# plug-v21-Make-board-myself-to-test-circu.net
KiCad netlist of a schematic drawn in EAGLE
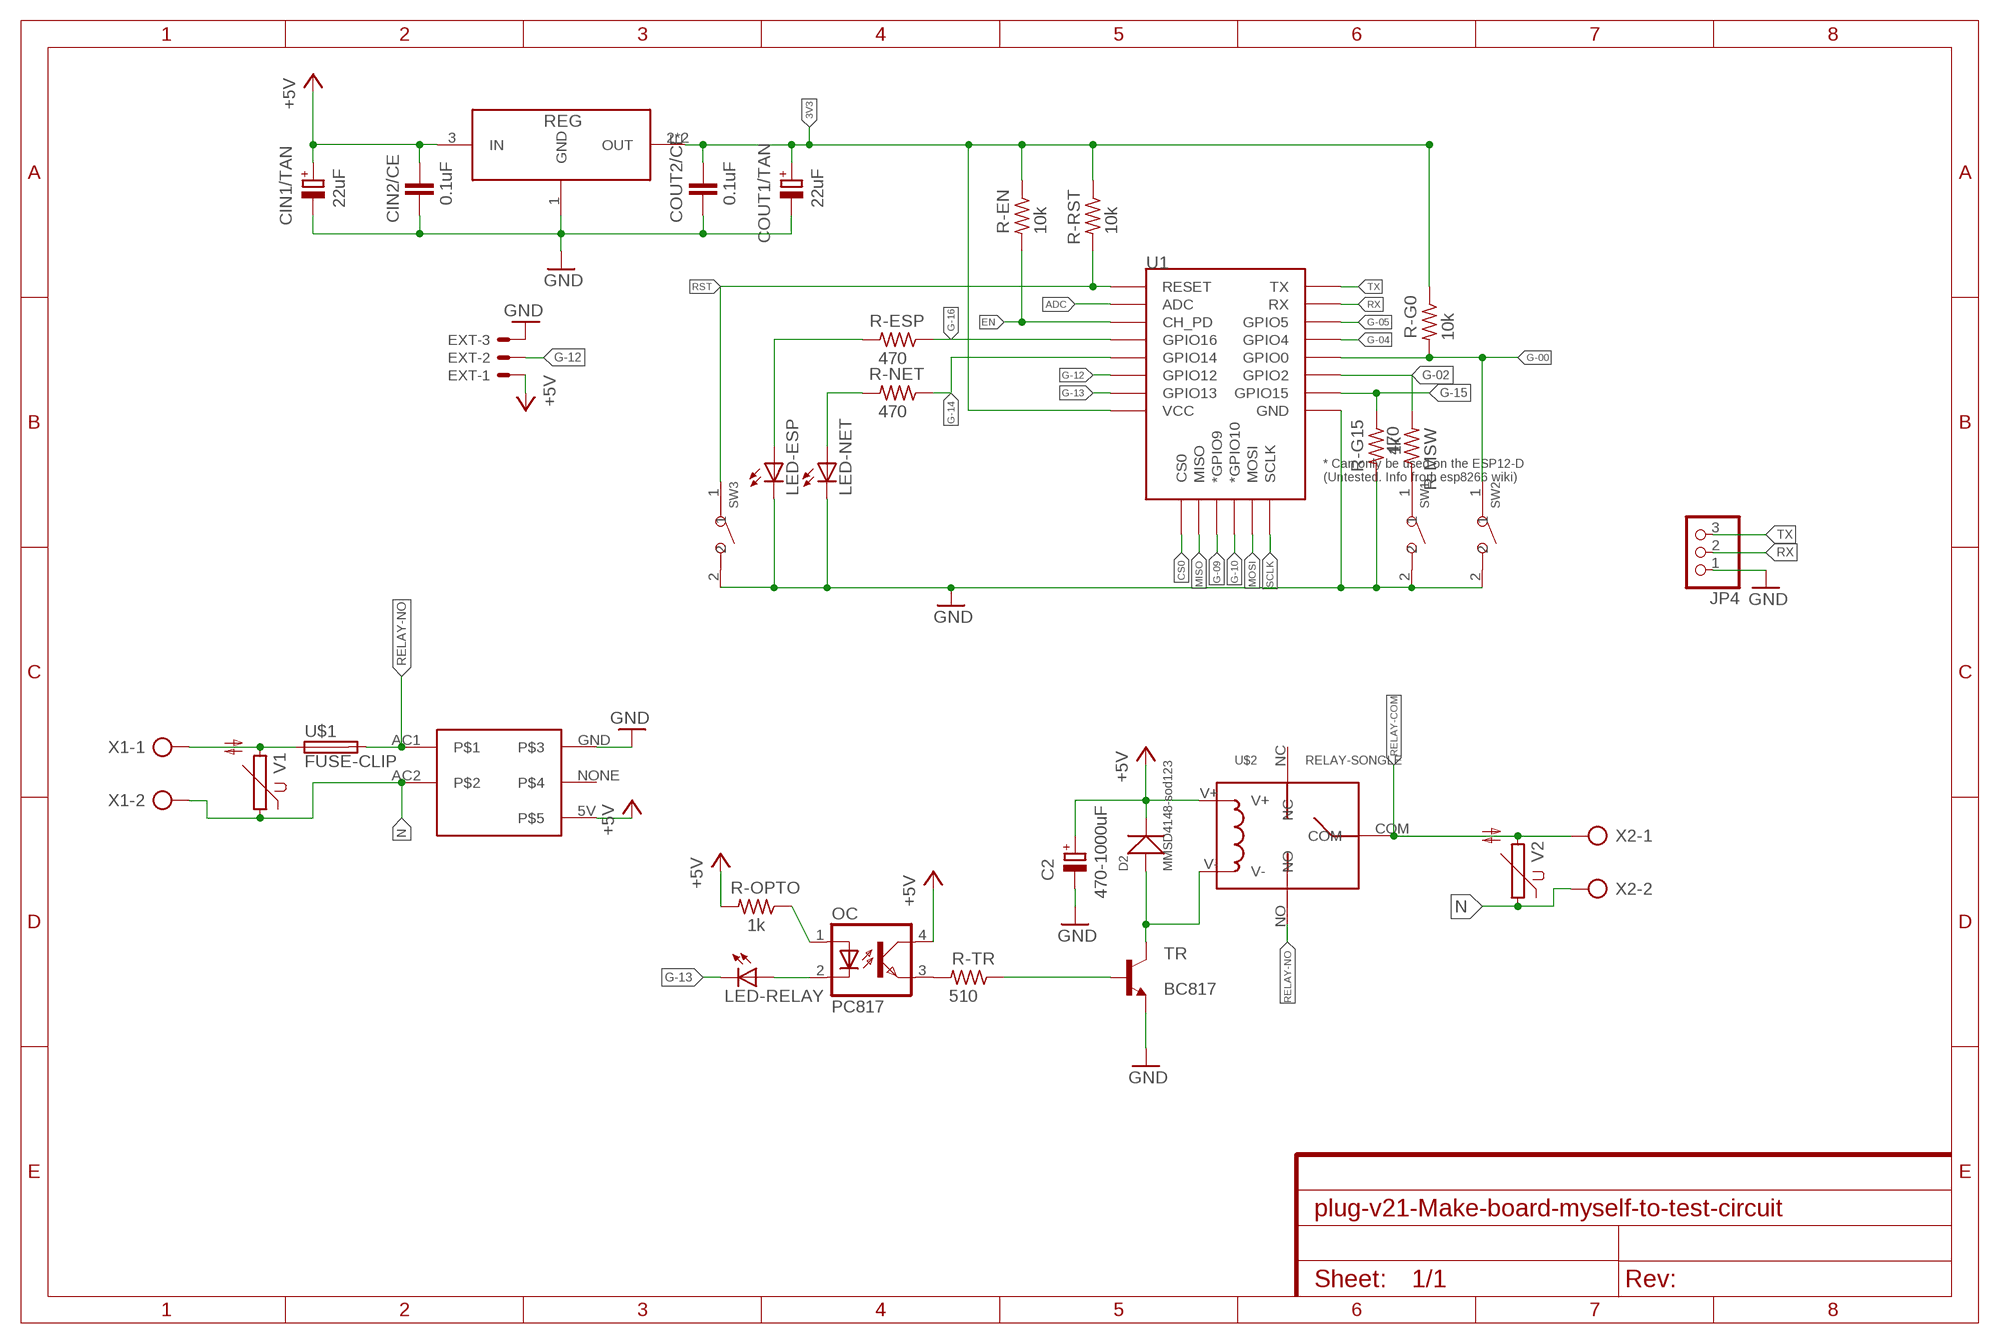
[diagram p0: schematic, sheet 1]

(export (version "E")
  (design (tool "Eeschema 10.0.6"))
  (components
    (comp (ref "C2")
      (value "470-1000uF")
      (footprint "eagle-import:E3,5-8")
      (libsource (lib "eagle-import") (part "CPOL-EUE3.5-8"))
    )
    (comp (ref "CIN1/TAN")
      (value "22uF")
      (footprint "eagle-import:B_3528-21R")
      (libsource (lib "eagle-import") (part "CPOL-EUB/3528-21R"))
    )
    (comp (ref "CIN2/CE")
      (value "0.1uF")
      (footprint "eagle-import:C0805K")
      (libsource (lib "eagle-import") (part "C-EUC0805K"))
    )
    (comp (ref "COUT1/TAN")
      (value "22uF")
      (footprint "eagle-import:B_3528-21R")
      (libsource (lib "eagle-import") (part "CPOL-EUB/3528-21R"))
    )
    (comp (ref "COUT2/CE")
      (value "0.1uF")
      (footprint "eagle-import:C0805K")
      (libsource (lib "eagle-import") (part "C-EUC0805K"))
    )
    (comp (ref "D2")
      (value "MMSD4148-sod123")
      (footprint "eagle-import:SOD-123")
      (fields (field (name "MPN") "MMSD4148"))
      (libsource (lib "eagle-import") (part "SMD-DIODE-100V-200MA(SOD-123)"))
    )
    (comp (ref "EXT")
      (value "53048-03")
      (footprint "eagle-import:53048-03")
      (fields (field (name "MF") "WALDOM/MOLEX") (field (name "MPN") "53048-0310"))
      (libsource (lib "eagle-import") (part "53?-03048"))
    )
    (comp (ref "JP4")
      (value "PINHD-1X3")
      (footprint "eagle-import:1X03")
      (libsource (lib "eagle-import") (part "PINHD-1X3"))
    )
    (comp (ref "LED-ESP")
      (value "LEDCHIPLED_0805")
      (footprint "eagle-import:CHIPLED_0805")
      (libsource (lib "eagle-import") (part "LEDCHIPLED_0805"))
    )
    (comp (ref "LED-NET")
      (value "LEDCHIPLED_0805")
      (footprint "eagle-import:CHIPLED_0805")
      (libsource (lib "eagle-import") (part "LEDCHIPLED_0805"))
    )
    (comp (ref "LED-RELAY")
      (value "LEDCHIPLED_0805")
      (footprint "eagle-import:CHIPLED_0805")
      (libsource (lib "eagle-import") (part "LEDCHIPLED_0805"))
    )
    (comp (ref "OC")
      (value "PC817")
      (footprint "eagle-import:DIL04")
      (fields (field (name "MPN") "PC817X4J000F"))
      (libsource (lib "eagle-import") (part "PC817"))
    )
    (comp (ref "R-EN")
      (value "10k")
      (footprint "eagle-import:M0805")
      (libsource (lib "eagle-import") (part "R-US_M0805"))
    )
    (comp (ref "R-ESP")
      (value "470")
      (footprint "eagle-import:M0805")
      (libsource (lib "eagle-import") (part "R-US_M0805"))
    )
    (comp (ref "R-G0")
      (value "10k")
      (footprint "eagle-import:M0805")
      (libsource (lib "eagle-import") (part "R-US_M0805"))
    )
    (comp (ref "R-G15")
      (value "1k")
      (footprint "eagle-import:M0805")
      (libsource (lib "eagle-import") (part "R-US_M0805"))
    )
    (comp (ref "R-MSW")
      (value "470")
      (footprint "eagle-import:M0805")
      (libsource (lib "eagle-import") (part "R-US_M0805"))
    )
    (comp (ref "R-NET")
      (value "470")
      (footprint "eagle-import:M0805")
      (libsource (lib "eagle-import") (part "R-US_M0805"))
    )
    (comp (ref "R-OPTO")
      (value "1k")
      (footprint "eagle-import:M0805")
      (libsource (lib "eagle-import") (part "R-US_M0805"))
    )
    (comp (ref "R-RST")
      (value "10k")
      (footprint "eagle-import:M0805")
      (libsource (lib "eagle-import") (part "R-US_M0805"))
    )
    (comp (ref "R-TR")
      (value "510")
      (footprint "eagle-import:M0805")
      (libsource (lib "eagle-import") (part "R-US_M0805"))
    )
    (comp (ref "REG")
      (value "AMS1117-3.3")
      (footprint "eagle-import:SOT-223")
      (libsource (lib "eagle-import") (part "AMS1117-3.3"))
    )
    (comp (ref "SW1")
      (value "DIP-BUTTON(2P-6.0X3.0X4.3MM)-TS-1101F")
      (footprint "eagle-import:SW2-5.0-6.0X3.0X4.3MM")
      (libsource (lib "eagle-import") (part "DIP-BUTTON(2P-6.0X3.0X4.3MM)-TS-1101F"))
    )
    (comp (ref "SW2")
      (value "DIP-BUTTON(2P-6.0X3.0X4.3MM)-TS-1101F")
      (footprint "eagle-import:SW2-5.0-6.0X3.0X4.3MM")
      (libsource (lib "eagle-import") (part "DIP-BUTTON(2P-6.0X3.0X4.3MM)-TS-1101F"))
    )
    (comp (ref "SW3")
      (value "DIP-BUTTON(2P-6.0X3.0X4.3MM)-TS-1101F")
      (footprint "eagle-import:SW2-5.0-6.0X3.0X4.3MM")
      (libsource (lib "eagle-import") (part "DIP-BUTTON(2P-6.0X3.0X4.3MM)-TS-1101F"))
    )
    (comp (ref "TR")
      (value "BC817")
      (footprint "eagle-import:SOT23-BEC")
      (libsource (lib "eagle-import") (part "BC817SMD-16"))
    )
    (comp (ref "U$1")
      (value "FUSE-CLIP")
      (footprint "eagle-import:FUSE-CLIP")
      (libsource (lib "eagle-import") (part "FUSE-CLIP"))
    )
    (comp (ref "U$2")
      (value "RELAY-SONGLE")
      (footprint "eagle-import:RELAY-SONGLE")
      (libsource (lib "eagle-import") (part "RELAY-SONGLE"))
    )
    (comp (ref "U$4")
      (value "POWERSUPPLY-5V-700MA")
      (footprint "eagle-import:POWERSUPPLY-5V-700MA")
      (libsource (lib "eagle-import") (part "POWERSUPPLY-5V-700MA"))
    )
    (comp (ref "U1")
      (value "ESP12ESMD")
      (footprint "eagle-import:ESP12E-SMD")
      (libsource (lib "eagle-import") (part "ESP12ESMD"))
    )
    (comp (ref "V1")
      (value "S14K11")
      (footprint "eagle-import:S14K11")
      (libsource (lib "eagle-import") (part "S14K11"))
    )
    (comp (ref "V2")
      (value "S14K11")
      (footprint "eagle-import:S14K11")
      (libsource (lib "eagle-import") (part "S14K11"))
    )
    (comp (ref "X1")
      (value "AK300/2")
      (footprint "eagle-import:AK300_2")
      (libsource (lib "eagle-import") (part "AK300/2"))
    )
    (comp (ref "X2")
      (value "AK300/2")
      (footprint "eagle-import:AK300_2")
      (libsource (lib "eagle-import") (part "AK300/2"))
    )
  )
  (nets
    (net (code "1") (name "+5V") (class "Default")
      (node (ref "C2") (pin "+") (pinfunction "+_+") (pintype "passive"))
      (node (ref "CIN1/TAN") (pin "+") (pinfunction "+_+") (pintype "passive"))
      (node (ref "CIN2/CE") (pin "1") (pinfunction "1_1") (pintype "passive"))
      (node (ref "D2") (pin "-") (pinfunction "-_-") (pintype "passive"))
      (node (ref "EXT") (pin "1") (pinfunction "S_1") (pintype "passive"))
      (node (ref "OC") (pin "4") (pinfunction "COL_4") (pintype "passive"))
      (node (ref "R-OPTO") (pin "2") (pinfunction "2_2") (pintype "passive"))
      (node (ref "REG") (pin "3") (pinfunction "IN_3") (pintype "input"))
      (node (ref "U$2") (pin "V+") (pinfunction "V+_V+") (pintype "bidirectional"))
      (node (ref "U$4") (pin "5V") (pinfunction "P$5_5V") (pintype "bidirectional"))
    )
    (net (code "2") (name "3V3") (class "Default")
      (node (ref "COUT1/TAN") (pin "+") (pinfunction "+_+") (pintype "passive"))
      (node (ref "COUT2/CE") (pin "1") (pinfunction "1_1") (pintype "passive"))
      (node (ref "R-EN") (pin "1") (pinfunction "1_1") (pintype "passive"))
      (node (ref "R-G0") (pin "1") (pinfunction "1_1") (pintype "passive"))
      (node (ref "R-RST") (pin "1") (pinfunction "1_1") (pintype "passive"))
      (node (ref "REG") (pin "2") (pinfunction "OUT_2") (pintype "output"))
      (node (ref "REG") (pin "4") (pinfunction "OUT_4") (pintype "output"))
      (node (ref "U1") (pin "VCC") (pinfunction "VCC_VCC") (pintype "bidirectional"))
    )
    (net (code "3") (name "ADC") (class "Default")
      (node (ref "U1") (pin "ADC") (pinfunction "ADC_ADC") (pintype "bidirectional"))
    )
    (net (code "4") (name "CS0") (class "Default")
      (node (ref "U1") (pin "CS0") (pinfunction "CS0_CS0") (pintype "bidirectional"))
    )
    (net (code "5") (name "EN") (class "Default")
      (node (ref "R-EN") (pin "2") (pinfunction "2_2") (pintype "passive"))
      (node (ref "U1") (pin "CH_PD") (pinfunction "CH_PD_CH_PD") (pintype "bidirectional"))
    )
    (net (code "6") (name "G-00") (class "Default")
      (node (ref "R-G0") (pin "2") (pinfunction "2_2") (pintype "passive"))
      (node (ref "SW2") (pin "1") (pinfunction "1_1") (pintype "bidirectional"))
      (node (ref "U1") (pin "GPIO0") (pinfunction "GPIO0_GPIO0") (pintype "bidirectional"))
    )
    (net (code "7") (name "G-02") (class "Default")
      (node (ref "R-MSW") (pin "2") (pinfunction "2_2") (pintype "passive"))
      (node (ref "U1") (pin "GPIO2") (pinfunction "GPIO2_GPIO2") (pintype "bidirectional"))
    )
    (net (code "8") (name "G-04") (class "Default")
      (node (ref "U1") (pin "GPIO4") (pinfunction "GPIO4_GPIO4") (pintype "bidirectional"))
    )
    (net (code "9") (name "G-05") (class "Default")
      (node (ref "U1") (pin "GPIO5") (pinfunction "GPIO5_GPIO5") (pintype "bidirectional"))
    )
    (net (code "10") (name "G-09") (class "Default")
      (node (ref "U1") (pin "GPIO9") (pinfunction "*GPIO9_GPIO9") (pintype "bidirectional"))
    )
    (net (code "11") (name "G-10") (class "Default")
      (node (ref "U1") (pin "GPIO10") (pinfunction "*GPIO10_GPIO10") (pintype "bidirectional"))
    )
    (net (code "12") (name "G-12") (class "Default")
      (node (ref "EXT") (pin "2") (pinfunction "S_2") (pintype "passive"))
      (node (ref "U1") (pin "GPIO12") (pinfunction "GPIO12_GPIO12") (pintype "bidirectional"))
    )
    (net (code "13") (name "G-13") (class "Default")
      (node (ref "LED-RELAY") (pin "C") (pinfunction "C_C") (pintype "passive"))
      (node (ref "U1") (pin "GPIO13") (pinfunction "GPIO13_GPIO13") (pintype "bidirectional"))
    )
    (net (code "14") (name "G-14") (class "Default")
      (node (ref "R-NET") (pin "1") (pinfunction "1_1") (pintype "passive"))
      (node (ref "U1") (pin "GPIO14") (pinfunction "GPIO14_GPIO14") (pintype "bidirectional"))
    )
    (net (code "15") (name "G-15") (class "Default")
      (node (ref "R-G15") (pin "1") (pinfunction "1_1") (pintype "passive"))
      (node (ref "U1") (pin "GPIO15") (pinfunction "GPIO15_GPIO15") (pintype "bidirectional"))
    )
    (net (code "16") (name "G-16") (class "Default")
      (node (ref "R-ESP") (pin "1") (pinfunction "1_1") (pintype "passive"))
      (node (ref "U1") (pin "GPIO16") (pinfunction "GPIO16_GPIO16") (pintype "bidirectional"))
    )
    (net (code "17") (name "GND") (class "Default")
      (node (ref "C2") (pin "-") (pinfunction "-_-") (pintype "passive"))
      (node (ref "CIN1/TAN") (pin "-") (pinfunction "-_-") (pintype "passive"))
      (node (ref "CIN2/CE") (pin "2") (pinfunction "2_2") (pintype "passive"))
      (node (ref "COUT1/TAN") (pin "-") (pinfunction "-_-") (pintype "passive"))
      (node (ref "COUT2/CE") (pin "2") (pinfunction "2_2") (pintype "passive"))
      (node (ref "EXT") (pin "3") (pinfunction "S_3") (pintype "passive"))
      (node (ref "JP4") (pin "1") (pinfunction "1_1") (pintype "passive"))
      (node (ref "LED-ESP") (pin "C") (pinfunction "C_C") (pintype "passive"))
      (node (ref "LED-NET") (pin "C") (pinfunction "C_C") (pintype "passive"))
      (node (ref "R-G15") (pin "2") (pinfunction "2_2") (pintype "passive"))
      (node (ref "REG") (pin "1") (pinfunction "GND_1") (pintype "passive"))
      (node (ref "SW1") (pin "2") (pinfunction "2_2") (pintype "bidirectional"))
      (node (ref "SW2") (pin "2") (pinfunction "2_2") (pintype "bidirectional"))
      (node (ref "SW3") (pin "2") (pinfunction "2_2") (pintype "bidirectional"))
      (node (ref "TR") (pin "E") (pinfunction "E_E") (pintype "passive"))
      (node (ref "U$4") (pin "GND") (pinfunction "P$3_GND") (pintype "bidirectional"))
      (node (ref "U1") (pin "GND") (pinfunction "GND_GND") (pintype "bidirectional"))
    )
    (net (code "18") (name "MISO") (class "Default")
      (node (ref "U1") (pin "MISO") (pinfunction "MISO_MISO") (pintype "bidirectional"))
    )
    (net (code "19") (name "MOSI") (class "Default")
      (node (ref "U1") (pin "MOSI") (pinfunction "MOSI_MOSI") (pintype "bidirectional"))
    )
    (net (code "20") (name "N") (class "Default")
      (node (ref "U$4") (pin "AC2") (pinfunction "P$2_AC2") (pintype "bidirectional"))
      (node (ref "V1") (pin "1") (pinfunction "1_1") (pintype "passive"))
      (node (ref "V2") (pin "1") (pinfunction "1_1") (pintype "passive"))
      (node (ref "X1") (pin "2") (pinfunction "KL_2") (pintype "passive"))
      (node (ref "X2") (pin "2") (pinfunction "KL_2") (pintype "passive"))
    )
    (net (code "21") (name "Net-(D2-Pad+)") (class "Default")
      (node (ref "D2") (pin "+") (pinfunction "+_+") (pintype "passive"))
      (node (ref "TR") (pin "C") (pinfunction "C_C") (pintype "passive"))
      (node (ref "U$2") (pin "V-") (pinfunction "V-_V-") (pintype "bidirectional"))
    )
    (net (code "22") (name "Net-(LED-ESP-PadA)") (class "Default")
      (node (ref "LED-ESP") (pin "A") (pinfunction "A_A") (pintype "passive"))
      (node (ref "R-ESP") (pin "2") (pinfunction "2_2") (pintype "passive"))
    )
    (net (code "23") (name "Net-(LED-NET-PadA)") (class "Default")
      (node (ref "LED-NET") (pin "A") (pinfunction "A_A") (pintype "passive"))
      (node (ref "R-NET") (pin "2") (pinfunction "2_2") (pintype "passive"))
    )
    (net (code "24") (name "Net-(OC-A)") (class "Default")
      (node (ref "OC") (pin "1") (pinfunction "A_1") (pintype "passive"))
      (node (ref "R-OPTO") (pin "1") (pinfunction "1_1") (pintype "passive"))
    )
    (net (code "25") (name "Net-(OC-C)") (class "Default")
      (node (ref "LED-RELAY") (pin "A") (pinfunction "A_A") (pintype "passive"))
      (node (ref "OC") (pin "2") (pinfunction "C_2") (pintype "passive"))
    )
    (net (code "26") (name "Net-(OC-EMIT)") (class "Default")
      (node (ref "OC") (pin "3") (pinfunction "EMIT_3") (pintype "passive"))
      (node (ref "R-TR") (pin "2") (pinfunction "2_2") (pintype "passive"))
    )
    (net (code "27") (name "Net-(R-MSW-Pad1)") (class "Default")
      (node (ref "R-MSW") (pin "1") (pinfunction "1_1") (pintype "passive"))
      (node (ref "SW1") (pin "1") (pinfunction "1_1") (pintype "bidirectional"))
    )
    (net (code "28") (name "Net-(R-TR-Pad1)") (class "Default")
      (node (ref "R-TR") (pin "1") (pinfunction "1_1") (pintype "passive"))
      (node (ref "TR") (pin "B") (pinfunction "B_B") (pintype "passive"))
    )
    (net (code "29") (name "Net-(X1A-KL)") (class "Default")
      (node (ref "U$1") (pin "3") (pinfunction "1_3") (pintype "passive"))
      (node (ref "U$1") (pin "4") (pinfunction "1_4") (pintype "passive"))
      (node (ref "V1") (pin "2") (pinfunction "2_2") (pintype "passive"))
      (node (ref "X1") (pin "1") (pinfunction "KL_1") (pintype "passive"))
    )
    (net (code "30") (name "RELAY-COM") (class "Default")
      (node (ref "U$2") (pin "COM") (pinfunction "COM_COM") (pintype "bidirectional"))
      (node (ref "V2") (pin "2") (pinfunction "2_2") (pintype "passive"))
      (node (ref "X2") (pin "1") (pinfunction "KL_1") (pintype "passive"))
    )
    (net (code "31") (name "RELAY-NO") (class "Default")
      (node (ref "U$1") (pin "5") (pinfunction "2_5") (pintype "passive"))
      (node (ref "U$1") (pin "6") (pinfunction "2_6") (pintype "passive"))
      (node (ref "U$2") (pin "NO") (pinfunction "NO_NO") (pintype "bidirectional"))
      (node (ref "U$4") (pin "AC1") (pinfunction "P$1_AC1") (pintype "bidirectional"))
    )
    (net (code "32") (name "RST") (class "Default")
      (node (ref "R-RST") (pin "2") (pinfunction "2_2") (pintype "passive"))
      (node (ref "SW3") (pin "1") (pinfunction "1_1") (pintype "bidirectional"))
      (node (ref "U1") (pin "RESET") (pinfunction "RESET_RESET") (pintype "bidirectional"))
    )
    (net (code "33") (name "RX") (class "Default")
      (node (ref "JP4") (pin "2") (pinfunction "2_2") (pintype "passive"))
      (node (ref "U1") (pin "RXD0") (pinfunction "RX_RXD0") (pintype "bidirectional"))
    )
    (net (code "34") (name "SCLK") (class "Default")
      (node (ref "U1") (pin "SCLK") (pinfunction "SCLK_SCLK") (pintype "bidirectional"))
    )
    (net (code "35") (name "TX") (class "Default")
      (node (ref "JP4") (pin "3") (pinfunction "3_3") (pintype "passive"))
      (node (ref "U1") (pin "TXD0") (pinfunction "TX_TXD0") (pintype "bidirectional"))
    )
    (net (code "36") (name "unconnected-(U$2-PadNC)") (class "Default")
      (node (ref "U$2") (pin "NC") (pinfunction "NC_NC") (pintype "bidirectional"))
    )
    (net (code "37") (name "unconnected-(U$4-P$4-PadNONE)") (class "Default")
      (node (ref "U$4") (pin "NONE") (pinfunction "P$4_NONE") (pintype "bidirectional"))
    )
  )
)
